# Controlador_de_temperatura.net
KiCad netlist of a schematic drawn in EAGLE
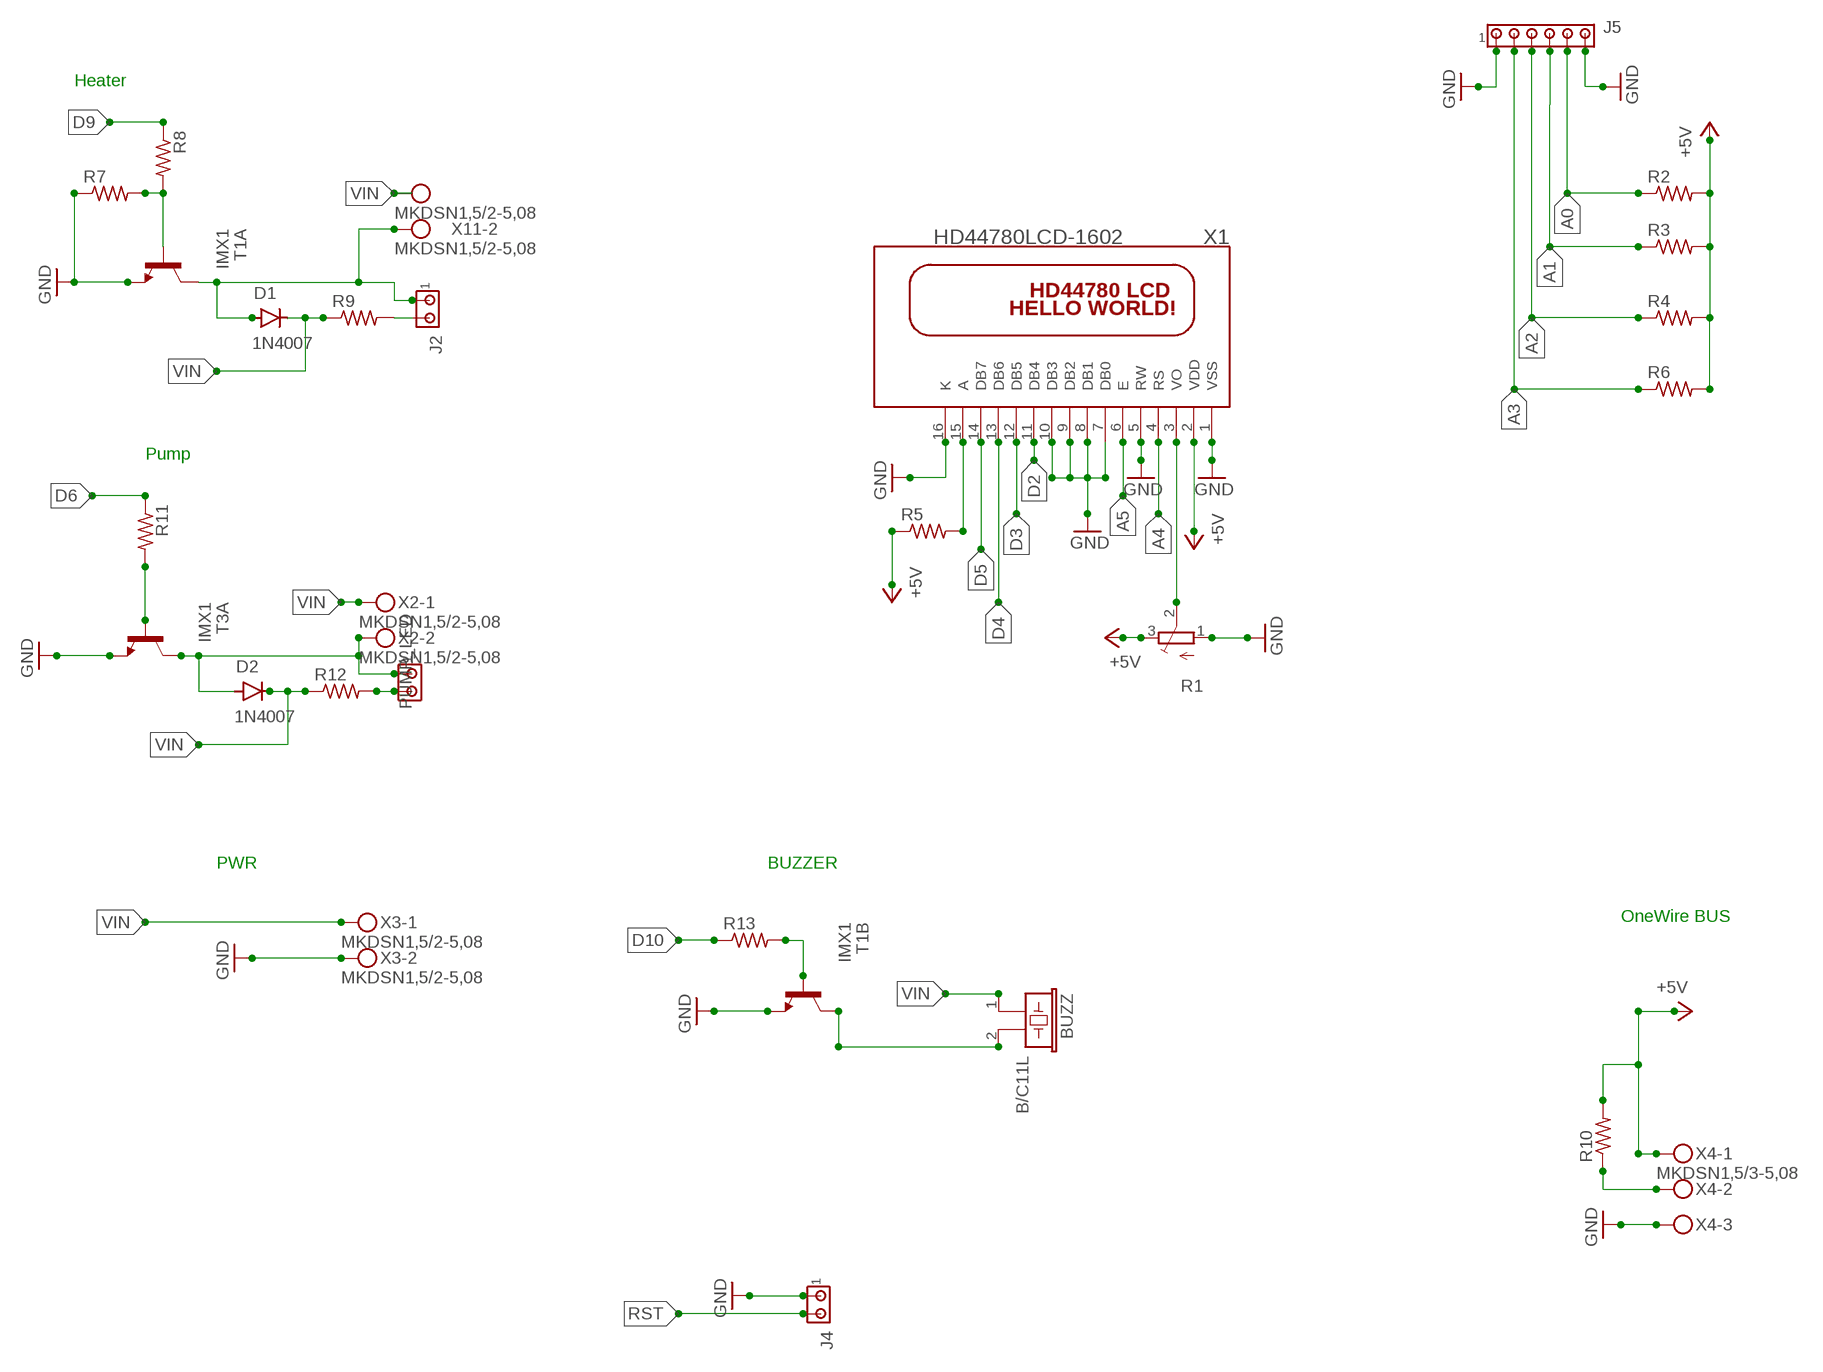
[diagram p0: schematic, sheet 1]

(export (version "E")
  (design (tool "Eeschema 10.0.6"))
  (components
    (comp (ref "BUZZ")
      (value "B/C11L")
      (footprint "eagle-import:B_C11L")
      (libsource (lib "eagle-import") (part "B/C11L"))
    )
    (comp (ref "D1")
      (value "1N4007")
      (footprint "eagle-import:DO-41")
      (fields
        (field (name "DIGIKEY_PART_NUMBER") "1N4007MSCT-ND")
        (field (name "MANUFACTURER") "Micro Commercial Co")
        (field (name "CREATED_BY") "PCBLayout.com")
      )
      (libsource (lib "eagle-import") (part "1N4007"))
    )
    (comp (ref "D2")
      (value "1N4007")
      (footprint "eagle-import:DO-41")
      (fields
        (field (name "DIGIKEY_PART_NUMBER") "1N4007MSCT-ND")
        (field (name "MANUFACTURER") "Micro Commercial Co")
        (field (name "CREATED_BY") "PCBLayout.com")
      )
      (libsource (lib "eagle-import") (part "1N4007"))
    )
    (comp (ref "J2")
      (value "MTA02-156")
      (footprint "eagle-import:1X2MTA")
      (libsource (lib "eagle-import") (part "MTA02-156"))
    )
    (comp (ref "J4")
      (value "MTA02-156")
      (footprint "eagle-import:1X2MTA")
      (libsource (lib "eagle-import") (part "MTA02-156"))
    )
    (comp (ref "J5")
      (value "MTA06-100")
      (footprint "eagle-import:10X06MTA")
      (libsource (lib "eagle-import") (part "MTA06-100"))
    )
    (comp (ref "PUMP_LED")
      (value "MTA02-156")
      (footprint "eagle-import:1X2MTA")
      (libsource (lib "eagle-import") (part "MTA02-156"))
    )
    (comp (ref "R1")
      (value "TRIM_EU-3223W")
      (footprint "eagle-import:3223W")
      (libsource (lib "eagle-import") (part "TRIM_EU-3223W"))
    )
    (comp (ref "R2")
      (value "R-US_0204/7")
      (footprint "eagle-import:0204_7")
      (libsource (lib "eagle-import") (part "R-US_0204/7"))
    )
    (comp (ref "R3")
      (value "R-US_0204/7")
      (footprint "eagle-import:0204_7")
      (libsource (lib "eagle-import") (part "R-US_0204/7"))
    )
    (comp (ref "R4")
      (value "R-US_0204/7")
      (footprint "eagle-import:0204_7")
      (libsource (lib "eagle-import") (part "R-US_0204/7"))
    )
    (comp (ref "R5")
      (value "R-US_0204/7")
      (footprint "eagle-import:0204_7")
      (libsource (lib "eagle-import") (part "R-US_0204/7"))
    )
    (comp (ref "R6")
      (value "R-US_0204/7")
      (footprint "eagle-import:0204_7")
      (libsource (lib "eagle-import") (part "R-US_0204/7"))
    )
    (comp (ref "R7")
      (value "R-US_0204/7")
      (footprint "eagle-import:0204_7")
      (libsource (lib "eagle-import") (part "R-US_0204/7"))
    )
    (comp (ref "R8")
      (value "R-US_0204/7")
      (footprint "eagle-import:0204_7")
      (libsource (lib "eagle-import") (part "R-US_0204/7"))
    )
    (comp (ref "R9")
      (value "R-US_0204/7")
      (footprint "eagle-import:0204_7")
      (libsource (lib "eagle-import") (part "R-US_0204/7"))
    )
    (comp (ref "R10")
      (value "R-US_0204/7")
      (footprint "eagle-import:0204_7")
      (libsource (lib "eagle-import") (part "R-US_0204/7"))
    )
    (comp (ref "R11")
      (value "R-US_0204/7")
      (footprint "eagle-import:0204_7")
      (libsource (lib "eagle-import") (part "R-US_0204/7"))
    )
    (comp (ref "R12")
      (value "R-US_0204/7")
      (footprint "eagle-import:0204_7")
      (libsource (lib "eagle-import") (part "R-US_0204/7"))
    )
    (comp (ref "R13")
      (value "R-US_0204/7")
      (footprint "eagle-import:0204_7")
      (libsource (lib "eagle-import") (part "R-US_0204/7"))
    )
    (comp (ref "T1")
      (value "IMX1")
      (footprint "eagle-import:SMT6")
      (fields (field (name "MPN") "IMX1T110"))
      (libsource (lib "eagle-import") (part "IMX1"))
    )
    (comp (ref "T3")
      (value "IMX1")
      (footprint "eagle-import:SMT6")
      (fields (field (name "MPN") "IMX1T110"))
      (libsource (lib "eagle-import") (part "IMX1"))
    )
    (comp (ref "X1")
      (value "HD44780LCD-1602")
      (footprint "eagle-import:LCD1602")
      (libsource (lib "eagle-import") (part "HD44780LCD-1602"))
    )
    (comp (ref "X2")
      (value "MKDSN1,5/2-5,08")
      (footprint "eagle-import:MKDSN1,5_2-5,08")
      (libsource (lib "eagle-import") (part "MKDSN1,5/2-5,08"))
    )
    (comp (ref "X3")
      (value "MKDSN1,5/2-5,08")
      (footprint "eagle-import:MKDSN1,5_2-5,08")
      (libsource (lib "eagle-import") (part "MKDSN1,5/2-5,08"))
    )
    (comp (ref "X4")
      (value "MKDSN1,5/3-5,08")
      (footprint "eagle-import:MKDSN1,5_3-5,08")
      (libsource (lib "eagle-import") (part "MKDSN1,5/3-5,08"))
    )
    (comp (ref "X11")
      (value "MKDSN1,5/2-5,08")
      (footprint "eagle-import:MKDSN1,5_2-5,08")
      (libsource (lib "eagle-import") (part "MKDSN1,5/2-5,08"))
    )
  )
  (nets
    (net (code "1") (name "+5V") (class "Default")
      (node (ref "R1") (pin "3") (pinfunction "E_3") (pintype "passive"))
      (node (ref "R10") (pin "2") (pinfunction "2_2") (pintype "passive"))
      (node (ref "R2") (pin "2") (pinfunction "2_2") (pintype "passive"))
      (node (ref "R3") (pin "2") (pinfunction "2_2") (pintype "passive"))
      (node (ref "R4") (pin "2") (pinfunction "2_2") (pintype "passive"))
      (node (ref "R5") (pin "1") (pinfunction "1_1") (pintype "passive"))
      (node (ref "R6") (pin "2") (pinfunction "2_2") (pintype "passive"))
      (node (ref "X1") (pin "2") (pinfunction "VDD_2") (pintype "power_in"))
      (node (ref "X4") (pin "1") (pinfunction "KL_1") (pintype "passive"))
    )
    (net (code "2") (name "A0") (class "Default")
      (node (ref "J5") (pin "5") (pinfunction "5_5") (pintype "passive"))
      (node (ref "R2") (pin "1") (pinfunction "1_1") (pintype "passive"))
    )
    (net (code "3") (name "A1") (class "Default")
      (node (ref "J5") (pin "4") (pinfunction "4_4") (pintype "passive"))
      (node (ref "R3") (pin "1") (pinfunction "1_1") (pintype "passive"))
    )
    (net (code "4") (name "A2") (class "Default")
      (node (ref "J5") (pin "3") (pinfunction "3_3") (pintype "passive"))
      (node (ref "R4") (pin "1") (pinfunction "1_1") (pintype "passive"))
    )
    (net (code "5") (name "A3") (class "Default")
      (node (ref "J5") (pin "2") (pinfunction "2_2") (pintype "passive"))
      (node (ref "R6") (pin "1") (pinfunction "1_1") (pintype "passive"))
    )
    (net (code "6") (name "A4") (class "Default")
      (node (ref "X1") (pin "4") (pinfunction "RS_4") (pintype "input"))
    )
    (net (code "7") (name "A5") (class "Default")
      (node (ref "X1") (pin "6") (pinfunction "E_6") (pintype "input"))
    )
    (net (code "8") (name "D2") (class "Default")
      (node (ref "X1") (pin "11") (pinfunction "DB4_11") (pintype "bidirectional"))
    )
    (net (code "9") (name "D3") (class "Default")
      (node (ref "X1") (pin "12") (pinfunction "DB5_12") (pintype "bidirectional"))
    )
    (net (code "10") (name "D4") (class "Default")
      (node (ref "X1") (pin "13") (pinfunction "DB6_13") (pintype "bidirectional"))
    )
    (net (code "11") (name "D5") (class "Default")
      (node (ref "X1") (pin "14") (pinfunction "DB7_14") (pintype "bidirectional"))
    )
    (net (code "12") (name "D6") (class "Default")
      (node (ref "R11") (pin "1") (pinfunction "1_1") (pintype "passive"))
    )
    (net (code "13") (name "D9") (class "Default")
      (node (ref "R8") (pin "1") (pinfunction "1_1") (pintype "passive"))
    )
    (net (code "14") (name "D10") (class "Default")
      (node (ref "R13") (pin "1") (pinfunction "1_1") (pintype "passive"))
    )
    (net (code "15") (name "GND") (class "Default")
      (node (ref "J4") (pin "1") (pinfunction "1_1") (pintype "passive"))
      (node (ref "J5") (pin "1") (pinfunction "1_1") (pintype "passive"))
      (node (ref "J5") (pin "6") (pinfunction "6_6") (pintype "passive"))
      (node (ref "R1") (pin "1") (pinfunction "A_1") (pintype "passive"))
      (node (ref "R7") (pin "1") (pinfunction "1_1") (pintype "passive"))
      (node (ref "T1") (pin "3") (pinfunction "E_3") (pintype "passive"))
      (node (ref "T1") (pin "6") (pinfunction "E_6") (pintype "passive"))
      (node (ref "T3") (pin "6") (pinfunction "E_6") (pintype "passive"))
      (node (ref "X1") (pin "1") (pinfunction "VSS_1") (pintype "power_in"))
      (node (ref "X1") (pin "10") (pinfunction "DB3_10") (pintype "bidirectional"))
      (node (ref "X1") (pin "16") (pinfunction "K_16") (pintype "input"))
      (node (ref "X1") (pin "5") (pinfunction "RW_5") (pintype "input"))
      (node (ref "X1") (pin "7") (pinfunction "DB0_7") (pintype "bidirectional"))
      (node (ref "X1") (pin "8") (pinfunction "DB1_8") (pintype "bidirectional"))
      (node (ref "X1") (pin "9") (pinfunction "DB2_9") (pintype "bidirectional"))
      (node (ref "X3") (pin "2") (pinfunction "KL_2") (pintype "passive"))
      (node (ref "X4") (pin "3") (pinfunction "KL_3") (pintype "passive"))
    )
    (net (code "16") (name "Net-(J2-Pad2)") (class "Default")
      (node (ref "J2") (pin "2") (pinfunction "2_2") (pintype "passive"))
      (node (ref "R9") (pin "2") (pinfunction "2_2") (pintype "passive"))
    )
    (net (code "17") (name "Net-(PUMP_LED-Pad2)") (class "Default")
      (node (ref "PUMP_LED") (pin "2") (pinfunction "2_2") (pintype "passive"))
      (node (ref "R12") (pin "2") (pinfunction "2_2") (pintype "passive"))
    )
    (net (code "18") (name "Net-(R1-S)") (class "Default")
      (node (ref "R1") (pin "2") (pinfunction "S_2") (pintype "passive"))
      (node (ref "X1") (pin "3") (pinfunction "VO_3") (pintype "input"))
    )
    (net (code "19") (name "Net-(T1A-B)") (class "Default")
      (node (ref "R7") (pin "2") (pinfunction "2_2") (pintype "passive"))
      (node (ref "R8") (pin "2") (pinfunction "2_2") (pintype "passive"))
      (node (ref "T1") (pin "5") (pinfunction "B_5") (pintype "passive"))
    )
    (net (code "20") (name "Net-(T1A-C)") (class "Default")
      (node (ref "D1") (pin "A") (pinfunction "A_A") (pintype "passive"))
      (node (ref "J2") (pin "1") (pinfunction "1_1") (pintype "passive"))
      (node (ref "T1") (pin "1") (pinfunction "C_1") (pintype "passive"))
      (node (ref "X11") (pin "2") (pinfunction "KL_2") (pintype "passive"))
    )
    (net (code "21") (name "Net-(T1B-B)") (class "Default")
      (node (ref "R13") (pin "2") (pinfunction "2_2") (pintype "passive"))
      (node (ref "T1") (pin "2") (pinfunction "B_2") (pintype "passive"))
    )
    (net (code "22") (name "Net-(T1B-C)") (class "Default")
      (node (ref "BUZZ") (pin "2") (pinfunction "2_2") (pintype "passive"))
      (node (ref "T1") (pin "4") (pinfunction "C_4") (pintype "passive"))
    )
    (net (code "23") (name "Net-(T3A-B)") (class "Default")
      (node (ref "R11") (pin "2") (pinfunction "2_2") (pintype "passive"))
      (node (ref "T3") (pin "5") (pinfunction "B_5") (pintype "passive"))
    )
    (net (code "24") (name "Net-(T3A-C)") (class "Default")
      (node (ref "D2") (pin "A") (pinfunction "A_A") (pintype "passive"))
      (node (ref "PUMP_LED") (pin "1") (pinfunction "1_1") (pintype "passive"))
      (node (ref "T3") (pin "1") (pinfunction "C_1") (pintype "passive"))
      (node (ref "X2") (pin "2") (pinfunction "KL_2") (pintype "passive"))
    )
    (net (code "25") (name "Net-(X1-A)") (class "Default")
      (node (ref "R5") (pin "2") (pinfunction "2_2") (pintype "passive"))
      (node (ref "X1") (pin "15") (pinfunction "A_15") (pintype "input"))
    )
    (net (code "26") (name "Net-(X4B-KL)") (class "Default")
      (node (ref "R10") (pin "1") (pinfunction "1_1") (pintype "passive"))
      (node (ref "X4") (pin "2") (pinfunction "KL_2") (pintype "passive"))
    )
    (net (code "27") (name "RST") (class "Default")
      (node (ref "J4") (pin "2") (pinfunction "2_2") (pintype "passive"))
    )
    (net (code "28") (name "VIN") (class "Default")
      (node (ref "BUZZ") (pin "1") (pinfunction "1_1") (pintype "passive"))
      (node (ref "D1") (pin "C") (pinfunction "C_C") (pintype "passive"))
      (node (ref "D2") (pin "C") (pinfunction "C_C") (pintype "passive"))
      (node (ref "R12") (pin "1") (pinfunction "1_1") (pintype "passive"))
      (node (ref "R9") (pin "1") (pinfunction "1_1") (pintype "passive"))
      (node (ref "X11") (pin "1") (pinfunction "KL_1") (pintype "passive"))
      (node (ref "X2") (pin "1") (pinfunction "KL_1") (pintype "passive"))
      (node (ref "X3") (pin "1") (pinfunction "KL_1") (pintype "passive"))
    )
  )
)
